# POWER.net
KiCad netlist of a schematic drawn in Altium Designer
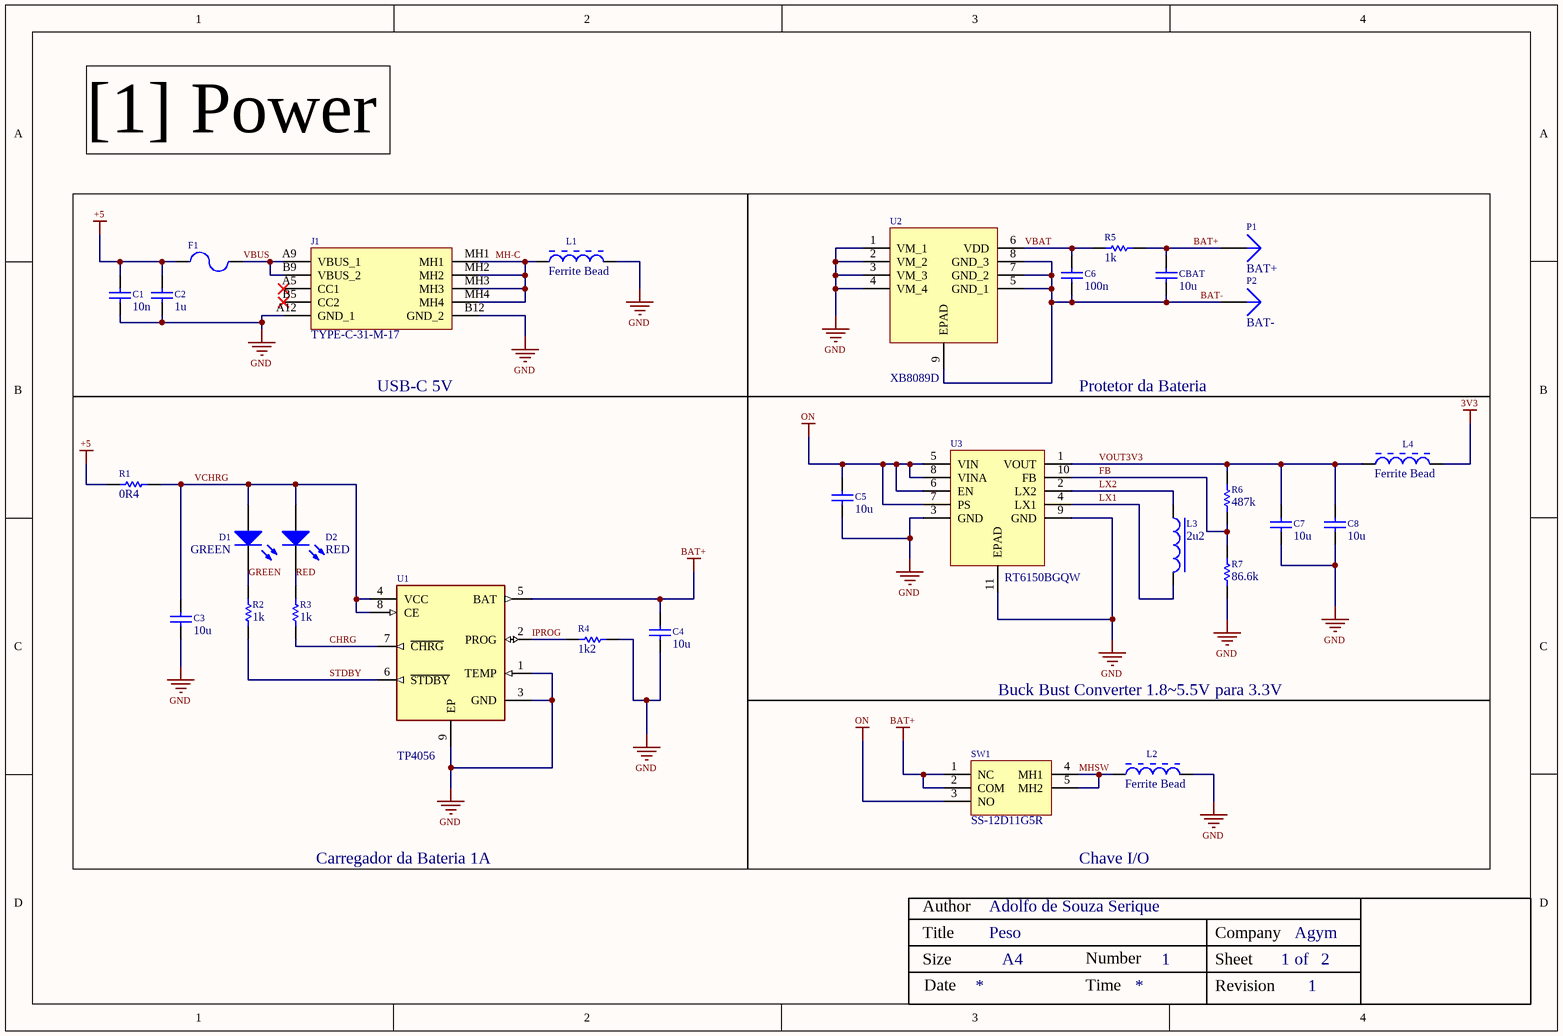
[diagram p0: POWER.SchDoc]

(export (version "E")
  (design (tool "Eeschema 10.0.6"))
  (components
    (comp (ref "C1")
      (value "10n")
      (footprint "C2012[0805]")
      (description "CAP CER 10000PF 50V C0G/NP0 0805")
      (fields (field (name "MANUFACTURER PART NUMBER") "CL21C103JBFNNNE") (field (name "TOLERANCE") "5%"))
      (libsource (lib "Basic Library") (part "C"))
    )
    (comp (ref "C2")
      (value "1u")
      (footprint "C2012[0805]")
      (description "CAP CER 1UF 50V X7R 0805")
      (fields (field (name "MANUFACTURER PART NUMBER") "CL21B105KBFNNNE") (field (name "TOLERANCE") "10%"))
      (libsource (lib "Basic Library") (part "C"))
    )
    (comp (ref "C3")
      (value "10u")
      (footprint "C3216[1206]")
      (description "Ceramic capacitor SMD-1206 10000nF (10uF) /25V X7R# K 10%, Samsung, RoHS/4k/")
      (fields (field (name "MANUFACTURER PART NUMBER") "CL31B106KAHNNNE") (field (name "TOLERANCE") "10%"))
      (libsource (lib "Basic Library") (part "C"))
    )
    (comp (ref "C4")
      (value "10u")
      (footprint "C3216[1206]")
      (description "Ceramic capacitor SMD-1206 10000nF (10uF) /25V X7R# K 10%, Samsung, RoHS/4k/")
      (fields (field (name "MANUFACTURER PART NUMBER") "CL31B106KAHNNNE") (field (name "TOLERANCE") "10%"))
      (libsource (lib "Basic Library") (part "C"))
    )
    (comp (ref "C5")
      (value "10u")
      (footprint "C2012[0805]")
      (description "Cap Ceramic 10uF 16V X7R 10% SMD 0805 125°C Emboss T/R")
      (fields (field (name "MANUFACTURER PART NUMBER") "CL21B106KOQNNNE") (field (name "TOLERANCE") "10%"))
      (libsource (lib "Basic Library") (part "C"))
    )
    (comp (ref "C6")
      (value "100n")
      (footprint "C2012[0805]")
      (description "CAP CER 0.1UF 50V X7R 0805")
      (fields (field (name "MANUFACTURER PART NUMBER") "CL21B104JBCNNNC") (field (name "TOLERANCE") "5%"))
      (libsource (lib "Basic Library") (part "C"))
    )
    (comp (ref "C7")
      (value "10u")
      (footprint "C2012[0805]")
      (description "Cap Ceramic 10uF 16V X7R 10% SMD 0805 125°C Emboss T/R")
      (fields (field (name "MANUFACTURER PART NUMBER") "CL21B106KOQNNNE") (field (name "TOLERANCE") "10%"))
      (libsource (lib "Basic Library") (part "C"))
    )
    (comp (ref "C8")
      (value "10u")
      (footprint "C2012[0805]")
      (description "Cap Ceramic 10uF 16V X7R 10% SMD 0805 125°C Emboss T/R")
      (fields (field (name "MANUFACTURER PART NUMBER") "CL21B106KOQNNNE") (field (name "TOLERANCE") "10%"))
      (libsource (lib "Basic Library") (part "C"))
    )
    (comp (ref "CBAT")
      (value "10u")
      (footprint "C3216[1206]")
      (description "Ceramic capacitor SMD-1206 10000nF (10uF) /25V X7R# K 10%, Samsung, RoHS/4k/")
      (fields (field (name "MANUFACTURER PART NUMBER") "CL31B106KAHNNNE") (field (name "TOLERANCE") "10%"))
      (libsource (lib "Basic Library") (part "C"))
    )
    (comp (ref "D1")
      (value "GREEN")
      (footprint "LED-0603-G")
      (description "LED")
      (fields
        (field (name "MANUFACTURER") "Yongyu Photoelectric")
        (field (name "MANUFACTURER PART NUMBER") "SZYY0603G")
      )
      (libsource (lib "Basic Library") (part "LED"))
    )
    (comp (ref "D2")
      (value "RED")
      (footprint "LED-0603-R")
      (description "LED")
      (fields
        (field (name "MANUFACTURER") "Yongyu Photoelectric")
        (field (name "MANUFACTURER PART NUMBER") "SZYY0603R")
      )
      (libsource (lib "Basic Library") (part "LED"))
    )
    (comp (ref "F1")
      (value "Resettable Fuse")
      (footprint "0805")
      (fields
        (field (name "LCSC PART NUMBER") "C70062")
        (field (name "MANUFACTURER") "DOWO")
        (field (name "MANUFACTURER PART NUMBER") "SMD0805-110")
      )
      (libsource (lib "Minha_Biblioteca") (part "Resettable Fuse"))
    )
    (comp (ref "J1")
      (value "TYPE-C-31-M-17")
      (footprint "TYPE C - 6 PINS")
      (description "6 Pins USB Type C")
      (fields
        (field (name "MANUFACTURER") "Korean Hroparts Elec")
        (field (name "LCSC PART NUMBER") "C283540")
      )
      (libsource (lib "Minha_Biblioteca") (part "TYPE-C-31-M-17"))
    )
    (comp (ref "L1")
      (value "Ferrite Bead")
      (footprint "0805")
      (description "Ferrite Beads Multi-Layer 220Ohm 25% 100MHz 2A 45mOhm DCR 0805 Paper T/R")
      (fields (field (name "LCSC PART NUMBER") "C85840") (field (name "MANUFACTURER") "Murata"))
      (libsource (lib "Minha_Biblioteca") (part "Ferrite Bead"))
    )
    (comp (ref "L2")
      (value "Ferrite Bead")
      (footprint "0603")
      (description "Ferrite Beads Multi-Layer 220Ohm 25% 100MHz 1.4A 100mOhm DCR 0603 Paper T/R")
      (fields (field (name "LCSC PART NUMBER") "C80165") (field (name "MANUFACTURER") "TDK EPCOS"))
      (libsource (lib "Minha_Biblioteca") (part "Ferrite Bead"))
    )
    (comp (ref "L3")
      (value "2u2")
      (footprint "INDUTOR 3.2x2.5mm")
      (description "Indutor")
      (fields
        (field (name "LCSC PART NUMBER") "C285914")
        (field (name "MANUFACTURER PART NUMBER") "HEI322512A-2R2M-Q8")
      )
      (libsource (lib "Minha_Biblioteca") (part "Indutor"))
    )
    (comp (ref "L4")
      (value "Ferrite Bead")
      (footprint "0603")
      (description "Ferrite Beads Multi-Layer 220Ohm 25% 100MHz 1.4A 100mOhm DCR 0603 Paper T/R")
      (fields (field (name "LCSC PART NUMBER") "C80165") (field (name "MANUFACTURER") "TDK EPCOS"))
      (libsource (lib "Minha_Biblioteca") (part "Ferrite Bead"))
    )
    (comp (ref "P1")
      (value "BAT+")
      (footprint "PIN1")
      (description "Plug")
      (fields (field (name "PUBLISHER") "Altium Limited"))
      (libsource (lib "Miscellaneous Connectors") (part "Plug"))
    )
    (comp (ref "P2")
      (value "BAT-")
      (footprint "PIN1")
      (description "Plug")
      (fields (field (name "PUBLISHER") "Altium Limited"))
      (libsource (lib "Miscellaneous Connectors") (part "Plug"))
    )
    (comp (ref "R1")
      (value "0R4")
      (footprint "R3216[1206]")
      (description "Resistor")
      (fields
        (field (name "MANUFACTURER") "UNI-ROYAL")
        (field (name "MANUFACTURER PART NUMBER") "1206W4F400LT5E")
      )
      (libsource (lib "Basic Library") (part "R"))
    )
    (comp (ref "R2")
      (value "1k")
      (footprint "R1608[0603]")
      (description "ERJ Series 0603 1 kOhm 0.2 W ±0.1 % ±50ppm/°C Thick Film Chip Resistor")
      (fields (field (name "MANUFACTURER PART NUMBER") "ERJ-PB3B1001V") (field (name "TOLERANCE") "0.1%"))
      (libsource (lib "Basic Library") (part "R"))
    )
    (comp (ref "R3")
      (value "1k")
      (footprint "R1608[0603]")
      (description "ERJ Series 0603 1 kOhm 0.2 W ±0.1 % ±50ppm/°C Thick Film Chip Resistor")
      (fields (field (name "MANUFACTURER PART NUMBER") "ERJ-PB3B1001V") (field (name "TOLERANCE") "0.1%"))
      (libsource (lib "Basic Library") (part "R"))
    )
    (comp (ref "R4")
      (value "1k2")
      (footprint "R1608[0603]")
      (description "Resistor")
      (fields
        (field (name "MANUFACTURER") "UNI-ROYAL")
        (field (name "MANUFACTURER PART NUMBER") "0603WAF1201T5E")
      )
      (libsource (lib "Basic Library") (part "R"))
    )
    (comp (ref "R5")
      (value "1k")
      (footprint "R2012[0805]")
      (description "Res Thick Film 0805 1K Ohm 1% 0.4W ±100ppm/C Epoxy Resin Pad SMD Automotive T/R")
      (fields (field (name "MANUFACTURER PART NUMBER") "ESR10EZPF1001") (field (name "TOLERANCE") "1%"))
      (libsource (lib "Basic Library") (part "R"))
    )
    (comp (ref "R6")
      (value "487k")
      (footprint "R1608[0603]")
      (description "Res Thick Film 0603 487K Ohm 1% 1/10W ±100ppm/°C Molded SMD Punched Carrier T/R")
      (fields (field (name "MANUFACTURER PART NUMBER") "ERJ-3EKF4873V") (field (name "TOLERANCE") "1%"))
      (libsource (lib "Basic Library") (part "R"))
    )
    (comp (ref "R7")
      (value "86.6k")
      (footprint "R1608[0603]")
      (description "Res Thick Film 0603 86.6K Ohm 1% 1/10W ±100ppm/°C Molded SMD Punched Carrier T/R")
      (fields (field (name "MANUFACTURER PART NUMBER") "ERJ-3EKF8662V") (field (name "TOLERANCE") "1%"))
      (libsource (lib "Basic Library") (part "R"))
    )
    (comp (ref "SW1")
      (value "SS-12D11G5R")
      (footprint "SS-12D11G5R")
      (description "Slide Switch")
      (fields
        (field (name "MANUFACTURER") "XKB Industrial Precision")
        (field (name "LCSC PART NUMBER") "C692484")
      )
      (libsource (lib "Minha_Biblioteca") (part "SS-12D11G5R"))
    )
    (comp (ref "U1")
      (value "TP4056")
      (footprint "SOP8-EPAD")
      (description "Carregador bateria 1A")
      (fields (field (name "MANUFACTURER") "TPOWER") (field (name "LCSC PART NUMBER") "C382139"))
      (libsource (lib "Minha_Biblioteca") (part "TP4056"))
    )
    (comp (ref "U2")
      (value "XB8089D")
      (footprint "SOP8-EPAD")
      (description "BAT Protection")
      (fields (field (name "MANUFACTURER") "Xysemi") (field (name "LCSC PART NUMBER") "C79928"))
      (libsource (lib "Minha_Biblioteca") (part "XB8089D"))
    )
    (comp (ref "U3")
      (value "RT6150BGQW")
      (footprint "WDFN-10_EPAD 3x3")
      (description "Step-down-Step-Up 1.8V~5.5V 1.8V~5.5V 800mA 1.6A 1MHz")
      (fields (field (name "MANUFACTURER") "Richtek Tech") (field (name "LCSC PART NUMBER") "C147972"))
      (libsource (lib "Minha_Biblioteca") (part "RT6150BGQW"))
    )
  )
  (nets
    (net (code "1") (name "+5") (class "Default")
      (node (ref "C1") (pin "1") (pinfunction "1_1") (pintype "passive"))
      (node (ref "C2") (pin "2") (pinfunction "2_2") (pintype "passive"))
      (node (ref "F1") (pin "1") (pinfunction "1_1") (pintype "passive"))
      (node (ref "R1") (pin "1") (pinfunction "1_1") (pintype "passive"))
    )
    (net (code "2") (name "/BAT-") (class "Default")
      (node (ref "C6") (pin "1") (pinfunction "1_1") (pintype "passive"))
      (node (ref "CBAT") (pin "1") (pinfunction "1_1") (pintype "passive"))
      (node (ref "P2") (pin "1") (pinfunction "1_1") (pintype "passive"))
      (node (ref "U2") (pin "5") (pinfunction "GND_1_5") (pintype "passive"))
      (node (ref "U2") (pin "7") (pinfunction "GND_2_7") (pintype "passive"))
      (node (ref "U2") (pin "8") (pinfunction "GND_3_8") (pintype "passive"))
      (node (ref "U2") (pin "9") (pinfunction "EPAD_9") (pintype "passive"))
    )
    (net (code "3") (name "/CHRG") (class "Default")
      (node (ref "R3") (pin "1") (pinfunction "1_1") (pintype "passive"))
      (node (ref "U1") (pin "7") (pinfunction "~{CHRG}_7") (pintype "output"))
    )
    (net (code "4") (name "/FB") (class "Default")
      (node (ref "R6") (pin "1") (pinfunction "1_1") (pintype "passive"))
      (node (ref "R7") (pin "2") (pinfunction "2_2") (pintype "passive"))
      (node (ref "U3") (pin "10") (pinfunction "FB_10") (pintype "passive"))
    )
    (net (code "5") (name "/GREEN") (class "Default")
      (node (ref "D1") (pin "2") (pinfunction "K_2") (pintype "passive"))
      (node (ref "R2") (pin "2") (pinfunction "2_2") (pintype "passive"))
    )
    (net (code "6") (name "/IPROG") (class "Default")
      (node (ref "R4") (pin "1") (pinfunction "1_1") (pintype "passive"))
      (node (ref "U1") (pin "2") (pinfunction "PROG_2") (pintype "bidirectional"))
    )
    (net (code "7") (name "/LX1") (class "Default")
      (node (ref "L3") (pin "2") (pinfunction "2_2") (pintype "passive"))
      (node (ref "U3") (pin "4") (pinfunction "LX1_4") (pintype "passive"))
    )
    (net (code "8") (name "/LX2") (class "Default")
      (node (ref "L3") (pin "1") (pinfunction "1_1") (pintype "passive"))
      (node (ref "U3") (pin "2") (pinfunction "LX2_2") (pintype "passive"))
    )
    (net (code "9") (name "/MH-C") (class "Default")
      (node (ref "J1") (pin "MH1") (pinfunction "MH1_MH1") (pintype "passive"))
      (node (ref "J1") (pin "MH2") (pinfunction "MH2_MH2") (pintype "passive"))
      (node (ref "J1") (pin "MH3") (pinfunction "MH3_MH3") (pintype "passive"))
      (node (ref "J1") (pin "MH4") (pinfunction "MH4_MH4") (pintype "passive"))
      (node (ref "L1") (pin "1") (pinfunction "1_1") (pintype "passive"))
    )
    (net (code "10") (name "/MHSW") (class "Default")
      (node (ref "L2") (pin "1") (pinfunction "1_1") (pintype "passive"))
      (node (ref "SW1") (pin "4") (pinfunction "MH1_4") (pintype "passive"))
      (node (ref "SW1") (pin "5") (pinfunction "MH2_5") (pintype "passive"))
    )
    (net (code "11") (name "/RED") (class "Default")
      (node (ref "D2") (pin "2") (pinfunction "K_2") (pintype "passive"))
      (node (ref "R3") (pin "2") (pinfunction "2_2") (pintype "passive"))
    )
    (net (code "12") (name "/STDBY") (class "Default")
      (node (ref "R2") (pin "1") (pinfunction "1_1") (pintype "passive"))
      (node (ref "U1") (pin "6") (pinfunction "~{STDBY}_6") (pintype "output"))
    )
    (net (code "13") (name "/VBAT") (class "Default")
      (node (ref "C6") (pin "2") (pinfunction "2_2") (pintype "passive"))
      (node (ref "R5") (pin "1") (pinfunction "1_1") (pintype "passive"))
      (node (ref "U2") (pin "6") (pinfunction "VDD_6") (pintype "passive"))
    )
    (net (code "14") (name "/VBUS") (class "Default")
      (node (ref "F1") (pin "2") (pinfunction "2_2") (pintype "passive"))
      (node (ref "J1") (pin "A9") (pinfunction "VBUS_1_A9") (pintype "passive"))
      (node (ref "J1") (pin "B9") (pinfunction "VBUS_2_B9") (pintype "passive"))
    )
    (net (code "15") (name "/VCHRG") (class "Default")
      (node (ref "C3") (pin "2") (pinfunction "2_2") (pintype "passive"))
      (node (ref "D1") (pin "1") (pinfunction "A_1") (pintype "passive"))
      (node (ref "D2") (pin "1") (pinfunction "A_1") (pintype "passive"))
      (node (ref "R1") (pin "2") (pinfunction "2_2") (pintype "passive"))
      (node (ref "U1") (pin "4") (pinfunction "VCC_4") (pintype "power_in"))
      (node (ref "U1") (pin "8") (pinfunction "CE_8") (pintype "input"))
    )
    (net (code "16") (name "/VOUT3V3") (class "Default")
      (node (ref "C7") (pin "1") (pinfunction "1_1") (pintype "passive"))
      (node (ref "C8") (pin "1") (pinfunction "1_1") (pintype "passive"))
      (node (ref "L4") (pin "1") (pinfunction "1_1") (pintype "passive"))
      (node (ref "R6") (pin "2") (pinfunction "2_2") (pintype "passive"))
      (node (ref "U3") (pin "1") (pinfunction "VOUT_1") (pintype "passive"))
    )
    (net (code "17") (name "3V3") (class "Default")
      (node (ref "L4") (pin "2") (pinfunction "2_2") (pintype "passive"))
    )
    (net (code "18") (name "BAT+") (class "Default")
      (node (ref "C4") (pin "2") (pinfunction "2_2") (pintype "passive"))
      (node (ref "CBAT") (pin "2") (pinfunction "2_2") (pintype "passive"))
      (node (ref "P1") (pin "1") (pinfunction "1_1") (pintype "passive"))
      (node (ref "R5") (pin "2") (pinfunction "2_2") (pintype "passive"))
      (node (ref "SW1") (pin "1") (pinfunction "NC_1") (pintype "passive"))
      (node (ref "SW1") (pin "2") (pinfunction "COM_2") (pintype "passive"))
      (node (ref "U1") (pin "5") (pinfunction "BAT_5") (pintype "output"))
    )
    (net (code "19") (name "GND") (class "Default")
      (node (ref "C1") (pin "2") (pinfunction "2_2") (pintype "passive"))
      (node (ref "C2") (pin "1") (pinfunction "1_1") (pintype "passive"))
      (node (ref "C3") (pin "1") (pinfunction "1_1") (pintype "passive"))
      (node (ref "C4") (pin "1") (pinfunction "1_1") (pintype "passive"))
      (node (ref "C5") (pin "2") (pinfunction "2_2") (pintype "passive"))
      (node (ref "C7") (pin "2") (pinfunction "2_2") (pintype "passive"))
      (node (ref "C8") (pin "2") (pinfunction "2_2") (pintype "passive"))
      (node (ref "J1") (pin "A12") (pinfunction "GND_1_A12") (pintype "passive"))
      (node (ref "J1") (pin "B12") (pinfunction "GND_2_B12") (pintype "passive"))
      (node (ref "L1") (pin "2") (pinfunction "2_2") (pintype "passive"))
      (node (ref "L2") (pin "2") (pinfunction "2_2") (pintype "passive"))
      (node (ref "R4") (pin "2") (pinfunction "2_2") (pintype "passive"))
      (node (ref "R7") (pin "1") (pinfunction "1_1") (pintype "passive"))
      (node (ref "U1") (pin "1") (pinfunction "TEMP_1") (pintype "input"))
      (node (ref "U1") (pin "3") (pinfunction "GND_3") (pintype "power_in"))
      (node (ref "U1") (pin "9") (pinfunction "EP_9") (pintype "passive"))
      (node (ref "U2") (pin "1") (pinfunction "VM_1_1") (pintype "passive"))
      (node (ref "U2") (pin "2") (pinfunction "VM_2_2") (pintype "passive"))
      (node (ref "U2") (pin "3") (pinfunction "VM_3_3") (pintype "passive"))
      (node (ref "U2") (pin "4") (pinfunction "VM_4_4") (pintype "passive"))
      (node (ref "U3") (pin "11") (pinfunction "EPAD_11") (pintype "power_in"))
      (node (ref "U3") (pin "3") (pinfunction "GND_3") (pintype "passive"))
      (node (ref "U3") (pin "9") (pinfunction "GND_9") (pintype "passive"))
    )
    (net (code "20") (name "ON") (class "Default")
      (node (ref "C5") (pin "1") (pinfunction "1_1") (pintype "passive"))
      (node (ref "SW1") (pin "3") (pinfunction "NO_3") (pintype "passive"))
      (node (ref "U3") (pin "5") (pinfunction "VIN_5") (pintype "passive"))
      (node (ref "U3") (pin "6") (pinfunction "EN_6") (pintype "passive"))
      (node (ref "U3") (pin "7") (pinfunction "PS_7") (pintype "passive"))
      (node (ref "U3") (pin "8") (pinfunction "VINA_8") (pintype "passive"))
    )
    (net (code "21") (name "unconnected-(J1-CC1-PadA5)") (class "Default")
      (node (ref "J1") (pin "A5") (pinfunction "CC1_A5") (pintype "passive+no_connect"))
    )
    (net (code "22") (name "unconnected-(J1-CC2-PadB5)") (class "Default")
      (node (ref "J1") (pin "B5") (pinfunction "CC2_B5") (pintype "passive+no_connect"))
    )
  )
)
